# Stopper_alap_V14_qfn.net
KiCad netlist of a schematic drawn in EAGLE
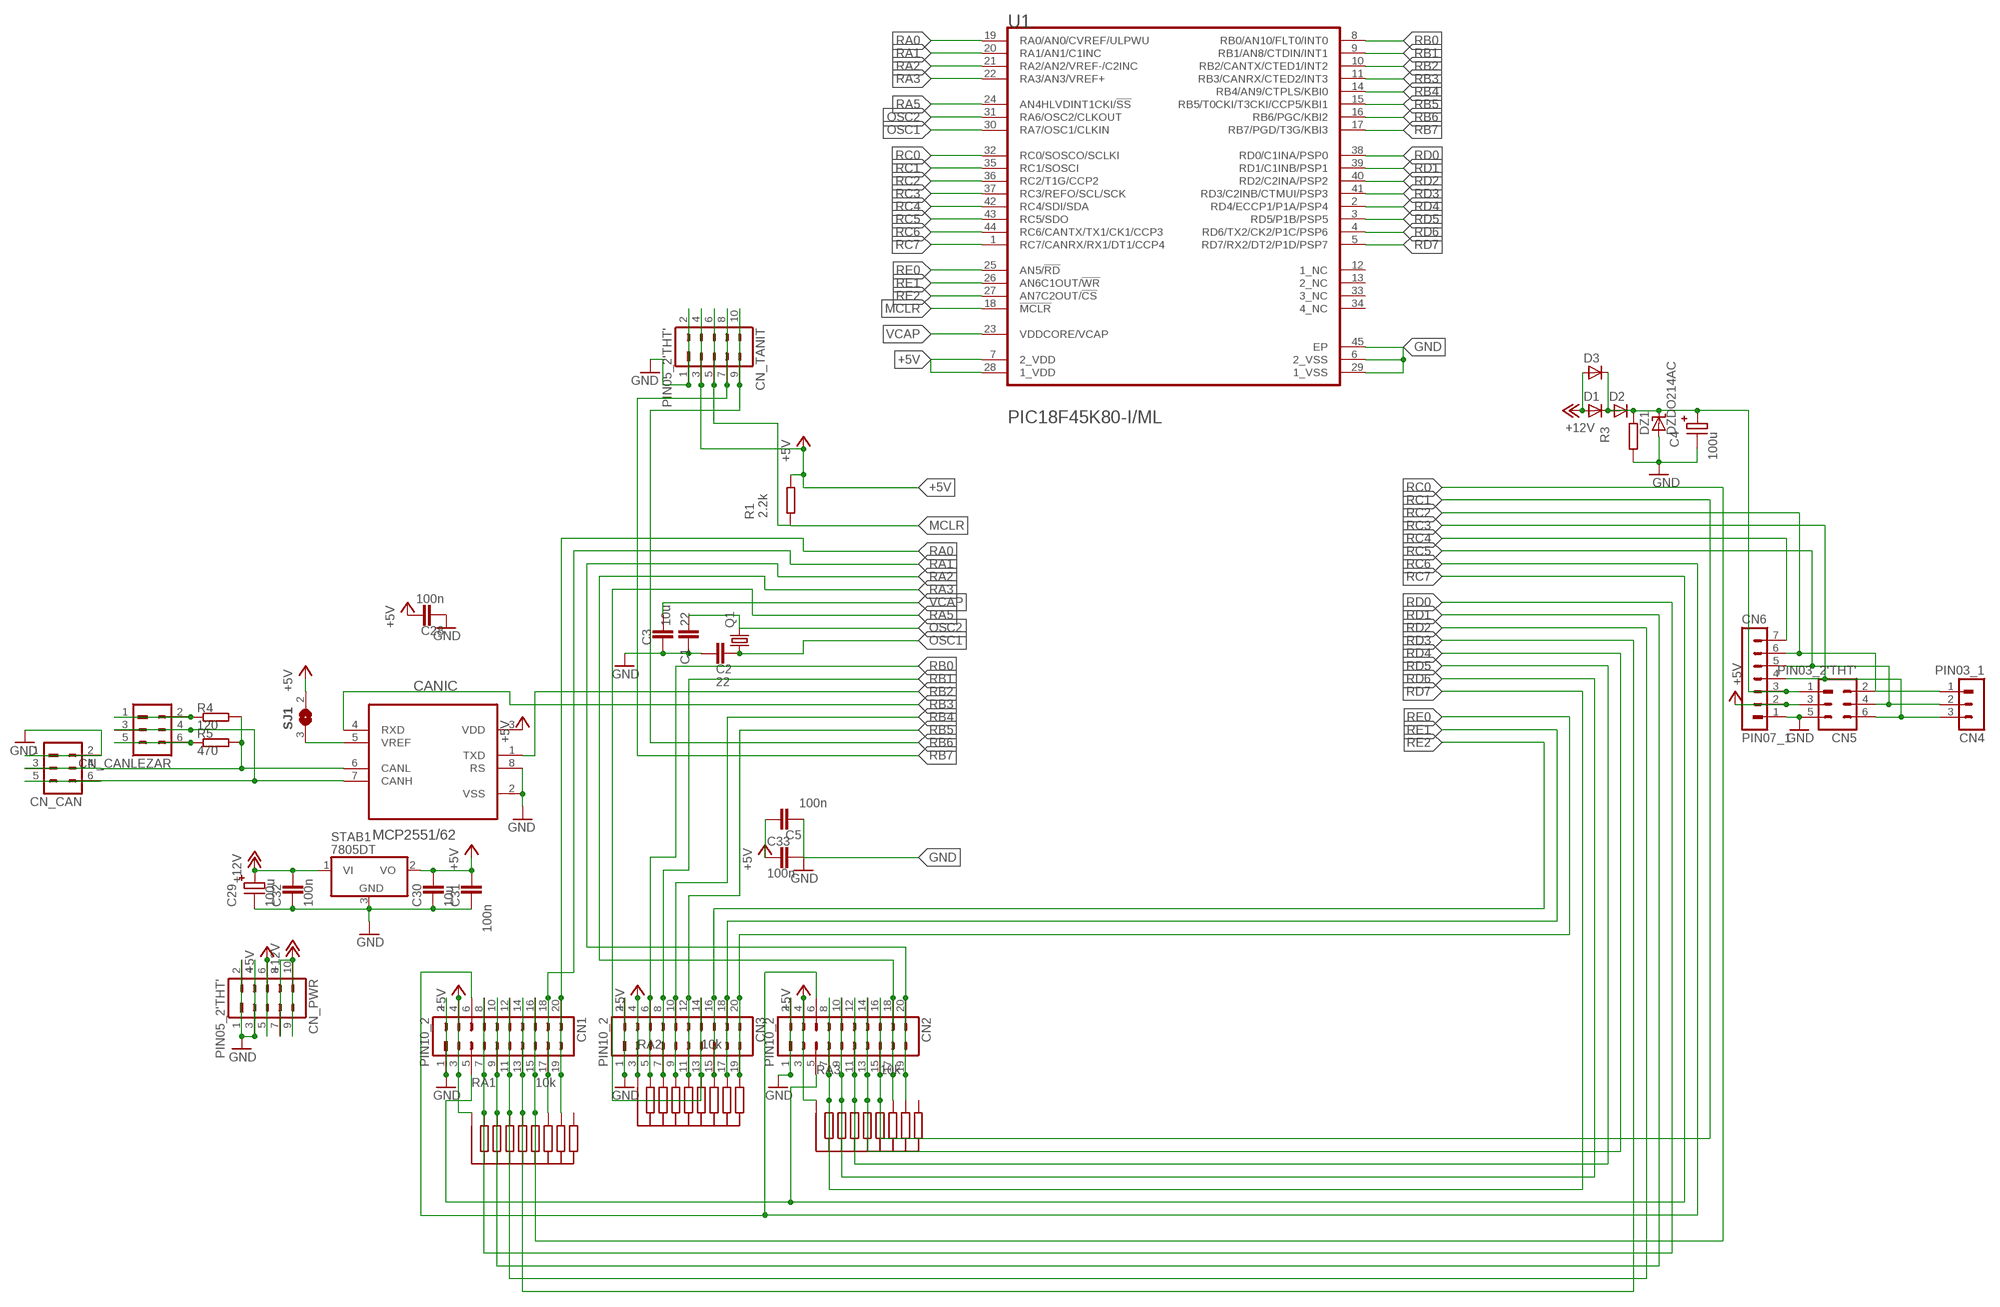
[diagram p0: schematic, sheet 1]

(export (version "E")
  (design (tool "Eeschema 10.0.6"))
  (components
    (comp (ref "C1")
      (value "22")
      (footprint "eagle-import:R0805")
      (libsource (lib "eagle-import") (part "C0805"))
    )
    (comp (ref "C2")
      (value "22")
      (footprint "eagle-import:R0805")
      (libsource (lib "eagle-import") (part "C0805"))
    )
    (comp (ref "C3")
      (value "10u")
      (footprint "eagle-import:R0805")
      (libsource (lib "eagle-import") (part "C0805"))
    )
    (comp (ref "C4")
      (value "100u")
      (footprint "eagle-import:C_EL1RASZT07")
      (libsource (lib "eagle-import") (part "C_EL1R07"))
    )
    (comp (ref "C5")
      (value "100n")
      (footprint "eagle-import:R0805")
      (libsource (lib "eagle-import") (part "C0805"))
    )
    (comp (ref "C28")
      (value "100n")
      (footprint "eagle-import:R0805")
      (libsource (lib "eagle-import") (part "C0805"))
    )
    (comp (ref "C29")
      (value "100u")
      (footprint "eagle-import:C_EL1RASZT07")
      (libsource (lib "eagle-import") (part "C_EL1R07"))
    )
    (comp (ref "C30")
      (value "10u")
      (footprint "eagle-import:R0805")
      (libsource (lib "eagle-import") (part "C0805"))
    )
    (comp (ref "C31")
      (value "100n")
      (footprint "eagle-import:R0805")
      (libsource (lib "eagle-import") (part "C0805"))
    )
    (comp (ref "C32")
      (value "100n")
      (footprint "eagle-import:R0805")
      (libsource (lib "eagle-import") (part "C0805"))
    )
    (comp (ref "C33")
      (value "100n")
      (footprint "eagle-import:R0805")
      (libsource (lib "eagle-import") (part "C0805"))
    )
    (comp (ref "CANIC")
      (value "MCP2551/62")
      (footprint "eagle-import:DIP254P762X432-8")
      (fields (field (name "MPN") "MCP2551-I/P"))
      (libsource (lib "eagle-import") (part "MCP2551-I/P"))
    )
    (comp (ref "CN1")
      (value "PIN10_2")
      (footprint "eagle-import:PIN10_2")
      (libsource (lib "eagle-import") (part "PIN10_2"))
    )
    (comp (ref "CN2")
      (value "PIN10_2")
      (footprint "eagle-import:PIN10_2")
      (libsource (lib "eagle-import") (part "PIN10_2"))
    )
    (comp (ref "CN3")
      (value "PIN10_2")
      (footprint "eagle-import:PIN10_2")
      (libsource (lib "eagle-import") (part "PIN10_2"))
    )
    (comp (ref "CN4")
      (value "PIN03_1")
      (footprint "eagle-import:PIN03_1")
      (libsource (lib "eagle-import") (part "PIN03_1"))
    )
    (comp (ref "CN5")
      (value "PIN03_2'THT'")
      (footprint "eagle-import:PIN03_2")
      (libsource (lib "eagle-import") (part "PIN03_2'THT'"))
    )
    (comp (ref "CN6")
      (value "PIN07_1")
      (footprint "eagle-import:PIN07_1")
      (libsource (lib "eagle-import") (part "PIN07_1"))
    )
    (comp (ref "CN_CAN")
      (value "PIN03_2'THT'")
      (footprint "eagle-import:PIN03_2")
      (libsource (lib "eagle-import") (part "PIN03_2'THT'"))
    )
    (comp (ref "CN_CANLEZAR")
      (value "PIN03_2'THT'")
      (footprint "eagle-import:PIN03_2")
      (libsource (lib "eagle-import") (part "PIN03_2'THT'"))
    )
    (comp (ref "CN_PWR")
      (value "PIN05_2'THT'")
      (footprint "eagle-import:PIN05_2")
      (libsource (lib "eagle-import") (part "PIN05_2'THT'"))
    )
    (comp (ref "CN_TANIT")
      (value "PIN05_2'THT'")
      (footprint "eagle-import:PIN05_2")
      (libsource (lib "eagle-import") (part "PIN05_2'THT'"))
    )
    (comp (ref "D1")
      (value "DDO214AC")
      (footprint "eagle-import:DO214AC")
      (libsource (lib "eagle-import") (part "DDO214AC"))
    )
    (comp (ref "D2")
      (value "DDO214AC")
      (footprint "eagle-import:DO214AC")
      (libsource (lib "eagle-import") (part "DDO214AC"))
    )
    (comp (ref "D3")
      (value "D1RNAGY")
      (footprint "eagle-import:D1RASZTNAGY")
      (libsource (lib "eagle-import") (part "D1RNAGY"))
    )
    (comp (ref "DZ1")
      (value "DZDO214AC")
      (footprint "eagle-import:DO214AC")
      (libsource (lib "eagle-import") (part "DZDO214AC"))
    )
    (comp (ref "Q1")
      (value "XTAL_2QS")
      (footprint "eagle-import:XTAL_QS")
      (libsource (lib "eagle-import") (part "XTAL_2QS"))
    )
    (comp (ref "R1")
      (value "2.2k")
      (footprint "eagle-import:R0805@1")
      (libsource (lib "eagle-import") (part "R_EU0805"))
    )
    (comp (ref "R3")
      (value "R_EU0805")
      (footprint "eagle-import:R0805@1")
      (libsource (lib "eagle-import") (part "R_EU0805"))
    )
    (comp (ref "R4")
      (value "120")
      (footprint "eagle-import:R0805@1")
      (libsource (lib "eagle-import") (part "R_EU0805"))
    )
    (comp (ref "R5")
      (value "470")
      (footprint "eagle-import:R0805@1")
      (libsource (lib "eagle-import") (part "R_EU0805"))
    )
    (comp (ref "RA1")
      (value "10k")
      (footprint "eagle-import:R_ARRAY")
      (libsource (lib "eagle-import") (part "R_ARRAY"))
    )
    (comp (ref "RA2")
      (value "10k")
      (footprint "eagle-import:R_ARRAY")
      (libsource (lib "eagle-import") (part "R_ARRAY"))
    )
    (comp (ref "RA3")
      (value "10k")
      (footprint "eagle-import:R_ARRAY")
      (libsource (lib "eagle-import") (part "R_ARRAY"))
    )
    (comp (ref "SJ1") (value "SJ") (footprint "eagle-import:SJ") (libsource (lib "eagle-import") (part "SJ")))
    (comp (ref "STAB1")
      (value "7805DT")
      (footprint "eagle-import:TO252")
      (libsource (lib "eagle-import") (part "78DT05"))
    )
    (comp (ref "U1")
      (value "MICROCHIP_PIC18F45K80-I-MLMICROCHIP_PIC18F45K80-I-ML_0_2")
      (footprint "eagle-import:MICROCHIP_PIC18F45K80-I-ML_2")
      (fields (field (name "MF") "Microchip") (field (name "MPN") "PIC18F45K80-I/ML"))
      (libsource (lib "eagle-import") (part "MICROCHIP_PIC18F45K80-I-MLMICROCHIP_PIC18F45K80-I-ML_0_2"))
    )
  )
  (nets
    (net (code "1") (name "+5V") (class "Default")
      (node (ref "C28") (pin "1") (pinfunction "1_1") (pintype "passive"))
      (node (ref "C30") (pin "1") (pinfunction "1_1") (pintype "passive"))
      (node (ref "C31") (pin "1") (pinfunction "1_1") (pintype "passive"))
      (node (ref "C33") (pin "2") (pinfunction "2_2") (pintype "passive"))
      (node (ref "C5") (pin "1") (pinfunction "1_1") (pintype "passive"))
      (node (ref "CANIC") (pin "3") (pinfunction "VDD_3") (pintype "power_in"))
      (node (ref "CN1") (pin "3") (pinfunction "3_3") (pintype "passive"))
      (node (ref "CN1") (pin "4") (pinfunction "4_4") (pintype "passive"))
      (node (ref "CN2") (pin "3") (pinfunction "3_3") (pintype "passive"))
      (node (ref "CN2") (pin "4") (pinfunction "4_4") (pintype "passive"))
      (node (ref "CN3") (pin "3") (pinfunction "3_3") (pintype "passive"))
      (node (ref "CN3") (pin "4") (pinfunction "4_4") (pintype "passive"))
      (node (ref "CN5") (pin "3") (pinfunction "3_3") (pintype "passive"))
      (node (ref "CN6") (pin "2") (pinfunction "2_2") (pintype "passive"))
      (node (ref "CN_PWR") (pin "5") (pinfunction "5_5") (pintype "passive"))
      (node (ref "CN_PWR") (pin "6") (pinfunction "6_6") (pintype "passive"))
      (node (ref "CN_TANIT") (pin "3") (pinfunction "3_3") (pintype "passive"))
      (node (ref "CN_TANIT") (pin "4") (pinfunction "4_4") (pintype "passive"))
      (node (ref "R1") (pin "2") (pinfunction "E_2") (pintype "passive"))
      (node (ref "RA1") (pin "P$1") (pinfunction "A_P$1") (pintype "passive"))
      (node (ref "RA2") (pin "P$1") (pinfunction "A_P$1") (pintype "passive"))
      (node (ref "RA3") (pin "P$1") (pinfunction "A_P$1") (pintype "passive"))
      (node (ref "SJ1") (pin "2") (pinfunction "2_2") (pintype "passive"))
      (node (ref "STAB1") (pin "2") (pinfunction "VO_2") (pintype "passive"))
      (node (ref "U1") (pin "28") (pinfunction "1_VDD_28") (pintype "power_in"))
      (node (ref "U1") (pin "7") (pinfunction "2_VDD_7") (pintype "power_in"))
    )
    (net (code "2") (name "+12V") (class "Default")
      (node (ref "C29") (pin "P+") (pinfunction "P+_P+") (pintype "passive"))
      (node (ref "C32") (pin "1") (pinfunction "1_1") (pintype "passive"))
      (node (ref "CN_PWR") (pin "10") (pinfunction "10_10") (pintype "passive"))
      (node (ref "CN_PWR") (pin "7") (pinfunction "7_7") (pintype "passive"))
      (node (ref "CN_PWR") (pin "8") (pinfunction "8_8") (pintype "passive"))
      (node (ref "CN_PWR") (pin "9") (pinfunction "9_9") (pintype "passive"))
      (node (ref "D1") (pin "A") (pinfunction "A_A") (pintype "passive"))
      (node (ref "D3") (pin "P$1") (pinfunction "A_P$1") (pintype "passive"))
      (node (ref "STAB1") (pin "1") (pinfunction "VI_1") (pintype "input"))
    )
    (net (code "3") (name "GND") (class "Default")
      (node (ref "C1") (pin "2") (pinfunction "2_2") (pintype "passive"))
      (node (ref "C2") (pin "2") (pinfunction "2_2") (pintype "passive"))
      (node (ref "C28") (pin "2") (pinfunction "2_2") (pintype "passive"))
      (node (ref "C29") (pin "P-") (pinfunction "P-_P-") (pintype "passive"))
      (node (ref "C3") (pin "2") (pinfunction "2_2") (pintype "passive"))
      (node (ref "C30") (pin "2") (pinfunction "2_2") (pintype "passive"))
      (node (ref "C31") (pin "2") (pinfunction "2_2") (pintype "passive"))
      (node (ref "C32") (pin "2") (pinfunction "2_2") (pintype "passive"))
      (node (ref "C33") (pin "1") (pinfunction "1_1") (pintype "passive"))
      (node (ref "C4") (pin "P-") (pinfunction "P-_P-") (pintype "passive"))
      (node (ref "C5") (pin "2") (pinfunction "2_2") (pintype "passive"))
      (node (ref "CANIC") (pin "2") (pinfunction "VSS_2") (pintype "power_in"))
      (node (ref "CANIC") (pin "8") (pinfunction "RS_8") (pintype "input"))
      (node (ref "CN1") (pin "1") (pinfunction "1_1") (pintype "passive"))
      (node (ref "CN1") (pin "2") (pinfunction "2_2") (pintype "passive"))
      (node (ref "CN2") (pin "1") (pinfunction "1_1") (pintype "passive"))
      (node (ref "CN2") (pin "2") (pinfunction "2_2") (pintype "passive"))
      (node (ref "CN3") (pin "1") (pinfunction "1_1") (pintype "passive"))
      (node (ref "CN3") (pin "2") (pinfunction "2_2") (pintype "passive"))
      (node (ref "CN5") (pin "5") (pinfunction "5_5") (pintype "passive"))
      (node (ref "CN6") (pin "1") (pinfunction "1_1") (pintype "passive"))
      (node (ref "CN_CAN") (pin "1") (pinfunction "1_1") (pintype "passive"))
      (node (ref "CN_CAN") (pin "2") (pinfunction "2_2") (pintype "passive"))
      (node (ref "CN_PWR") (pin "1") (pinfunction "1_1") (pintype "passive"))
      (node (ref "CN_PWR") (pin "2") (pinfunction "2_2") (pintype "passive"))
      (node (ref "CN_PWR") (pin "3") (pinfunction "3_3") (pintype "passive"))
      (node (ref "CN_PWR") (pin "4") (pinfunction "4_4") (pintype "passive"))
      (node (ref "CN_TANIT") (pin "1") (pinfunction "1_1") (pintype "passive"))
      (node (ref "CN_TANIT") (pin "2") (pinfunction "2_2") (pintype "passive"))
      (node (ref "DZ1") (pin "A") (pinfunction "A_A") (pintype "passive"))
      (node (ref "R3") (pin "1") (pinfunction "A_1") (pintype "passive"))
      (node (ref "STAB1") (pin "3") (pinfunction "GND_3") (pintype "passive"))
      (node (ref "U1") (pin "29") (pinfunction "1_VSS_29") (pintype "power_in"))
      (node (ref "U1") (pin "45") (pinfunction "EP_45") (pintype "power_in"))
      (node (ref "U1") (pin "6") (pinfunction "2_VSS_6") (pintype "power_in"))
    )
    (net (code "4") (name "MCLR") (class "Default")
      (node (ref "CN_TANIT") (pin "5") (pinfunction "5_5") (pintype "passive"))
      (node (ref "CN_TANIT") (pin "6") (pinfunction "6_6") (pintype "passive"))
      (node (ref "R1") (pin "1") (pinfunction "A_1") (pintype "passive"))
      (node (ref "U1") (pin "18") (pinfunction "~{MCLR}_18") (pintype "input"))
    )
    (net (code "5") (name "Net-(CANIC-CANH)") (class "Default")
      (node (ref "CANIC") (pin "7") (pinfunction "CANH_7") (pintype "bidirectional"))
      (node (ref "CN_CAN") (pin "5") (pinfunction "5_5") (pintype "passive"))
      (node (ref "CN_CAN") (pin "6") (pinfunction "6_6") (pintype "passive"))
      (node (ref "CN_CANLEZAR") (pin "3") (pinfunction "3_3") (pintype "passive"))
      (node (ref "CN_CANLEZAR") (pin "4") (pinfunction "4_4") (pintype "passive"))
    )
    (net (code "6") (name "Net-(CANIC-CANL)") (class "Default")
      (node (ref "CANIC") (pin "6") (pinfunction "CANL_6") (pintype "bidirectional"))
      (node (ref "CN_CAN") (pin "3") (pinfunction "3_3") (pintype "passive"))
      (node (ref "CN_CAN") (pin "4") (pinfunction "4_4") (pintype "passive"))
      (node (ref "R4") (pin "2") (pinfunction "E_2") (pintype "passive"))
      (node (ref "R5") (pin "1") (pinfunction "A_1") (pintype "passive"))
    )
    (net (code "7") (name "Net-(CANIC-VREF)") (class "Default")
      (node (ref "CANIC") (pin "5") (pinfunction "VREF_5") (pintype "output"))
      (node (ref "SJ1") (pin "3") (pinfunction "1_3") (pintype "passive"))
    )
    (net (code "8") (name "Net-(D3-C)") (class "Default")
      (node (ref "C4") (pin "P+") (pinfunction "P+_P+") (pintype "passive"))
      (node (ref "CN5") (pin "1") (pinfunction "1_1") (pintype "passive"))
      (node (ref "CN6") (pin "3") (pinfunction "3_3") (pintype "passive"))
      (node (ref "D1") (pin "C") (pinfunction "C_C") (pintype "passive"))
      (node (ref "D2") (pin "A") (pinfunction "A_A") (pintype "passive"))
      (node (ref "D2") (pin "C") (pinfunction "C_C") (pintype "passive"))
      (node (ref "D3") (pin "P$2") (pinfunction "C_P$2") (pintype "passive"))
      (node (ref "DZ1") (pin "C") (pinfunction "C_C") (pintype "passive"))
      (node (ref "R3") (pin "2") (pinfunction "E_2") (pintype "passive"))
    )
    (net (code "9") (name "Net-(R4-A)") (class "Default")
      (node (ref "CN_CANLEZAR") (pin "1") (pinfunction "1_1") (pintype "passive"))
      (node (ref "CN_CANLEZAR") (pin "2") (pinfunction "2_2") (pintype "passive"))
      (node (ref "R4") (pin "1") (pinfunction "A_1") (pintype "passive"))
    )
    (net (code "10") (name "Net-(R5-E)") (class "Default")
      (node (ref "CN_CANLEZAR") (pin "5") (pinfunction "5_5") (pintype "passive"))
      (node (ref "CN_CANLEZAR") (pin "6") (pinfunction "6_6") (pintype "passive"))
      (node (ref "R5") (pin "2") (pinfunction "E_2") (pintype "passive"))
    )
    (net (code "11") (name "OSC1") (class "Default")
      (node (ref "C2") (pin "1") (pinfunction "1_1") (pintype "passive"))
      (node (ref "Q1") (pin "1") (pinfunction "1_1") (pintype "passive"))
      (node (ref "U1") (pin "30") (pinfunction "RA7/OSC1/CLKIN_30") (pintype "bidirectional"))
    )
    (net (code "12") (name "OSC2") (class "Default")
      (node (ref "C1") (pin "1") (pinfunction "1_1") (pintype "passive"))
      (node (ref "Q1") (pin "2") (pinfunction "2_2") (pintype "passive"))
      (node (ref "U1") (pin "31") (pinfunction "RA6/OSC2/CLKOUT_31") (pintype "bidirectional"))
    )
    (net (code "13") (name "RA0") (class "Default")
      (node (ref "CN1") (pin "19") (pinfunction "19_19") (pintype "passive"))
      (node (ref "CN1") (pin "20") (pinfunction "20_20") (pintype "passive"))
      (node (ref "RA1") (pin "P$8") (pinfunction "E6_P$8") (pintype "passive"))
      (node (ref "U1") (pin "19") (pinfunction "RA0/AN0/CVREF/ULPWU_19") (pintype "bidirectional"))
    )
    (net (code "14") (name "RA1") (class "Default")
      (node (ref "CN1") (pin "17") (pinfunction "17_17") (pintype "passive"))
      (node (ref "CN1") (pin "18") (pinfunction "18_18") (pintype "passive"))
      (node (ref "RA1") (pin "P$7") (pinfunction "E5_P$7") (pintype "passive"))
      (node (ref "U1") (pin "20") (pinfunction "RA1/AN1/C1INC_20") (pintype "bidirectional"))
    )
    (net (code "15") (name "RA2") (class "Default")
      (node (ref "CN2") (pin "19") (pinfunction "19_19") (pintype "passive"))
      (node (ref "CN2") (pin "20") (pinfunction "20_20") (pintype "passive"))
      (node (ref "RA3") (pin "P$8") (pinfunction "E6_P$8") (pintype "passive"))
      (node (ref "U1") (pin "21") (pinfunction "RA2/AN2/VREF-/C2INC_21") (pintype "bidirectional"))
    )
    (net (code "16") (name "RA3") (class "Default")
      (node (ref "CN2") (pin "17") (pinfunction "17_17") (pintype "passive"))
      (node (ref "CN2") (pin "18") (pinfunction "18_18") (pintype "passive"))
      (node (ref "RA3") (pin "P$7") (pinfunction "E5_P$7") (pintype "passive"))
      (node (ref "U1") (pin "22") (pinfunction "RA3/AN3/VREF+_22") (pintype "bidirectional"))
    )
    (net (code "17") (name "RA5") (class "Default")
      (node (ref "CN3") (pin "13") (pinfunction "13_13") (pintype "passive"))
      (node (ref "CN3") (pin "14") (pinfunction "14_14") (pintype "passive"))
      (node (ref "RA2") (pin "P$6") (pinfunction "E4_P$6") (pintype "passive"))
      (node (ref "U1") (pin "24") (pinfunction "AN4HLVDINT1CKI/~{SS}_24") (pintype "bidirectional"))
    )
    (net (code "18") (name "RB0") (class "Default")
      (node (ref "CN3") (pin "5") (pinfunction "5_5") (pintype "passive"))
      (node (ref "CN3") (pin "6") (pinfunction "6_6") (pintype "passive"))
      (node (ref "RA2") (pin "P$2") (pinfunction "E_P$2") (pintype "passive"))
      (node (ref "U1") (pin "8") (pinfunction "RB0/AN10/FLT0/INT0_8") (pintype "bidirectional"))
    )
    (net (code "19") (name "RB1") (class "Default")
      (node (ref "CN3") (pin "7") (pinfunction "7_7") (pintype "passive"))
      (node (ref "CN3") (pin "8") (pinfunction "8_8") (pintype "passive"))
      (node (ref "RA2") (pin "P$3") (pinfunction "E1_P$3") (pintype "passive"))
      (node (ref "U1") (pin "9") (pinfunction "RB1/AN8/CTDIN/INT1_9") (pintype "bidirectional"))
    )
    (net (code "20") (name "RB2") (class "Default")
      (node (ref "CANIC") (pin "1") (pinfunction "TXD_1") (pintype "input"))
      (node (ref "U1") (pin "10") (pinfunction "RB2/CANTX/CTED1/INT2_10") (pintype "bidirectional"))
    )
    (net (code "21") (name "RB3") (class "Default")
      (node (ref "CANIC") (pin "4") (pinfunction "RXD_4") (pintype "output"))
      (node (ref "U1") (pin "11") (pinfunction "RB3/CANRX/CTED2/INT3_11") (pintype "bidirectional"))
    )
    (net (code "22") (name "RB4") (class "Default")
      (node (ref "CN3") (pin "10") (pinfunction "10_10") (pintype "passive"))
      (node (ref "CN3") (pin "9") (pinfunction "9_9") (pintype "passive"))
      (node (ref "RA2") (pin "P$4") (pinfunction "E2_P$4") (pintype "passive"))
      (node (ref "U1") (pin "14") (pinfunction "RB4/AN9/CTPLS/KBI0_14") (pintype "bidirectional"))
    )
    (net (code "23") (name "RB5") (class "Default")
      (node (ref "CN3") (pin "11") (pinfunction "11_11") (pintype "passive"))
      (node (ref "CN3") (pin "12") (pinfunction "12_12") (pintype "passive"))
      (node (ref "RA2") (pin "P$5") (pinfunction "E3_P$5") (pintype "passive"))
      (node (ref "U1") (pin "15") (pinfunction "RB5/T0CKI/T3CKI/CCP5/KBI1_15") (pintype "bidirectional"))
    )
    (net (code "24") (name "RB6") (class "Default")
      (node (ref "CN_TANIT") (pin "10") (pinfunction "10_10") (pintype "passive"))
      (node (ref "CN_TANIT") (pin "9") (pinfunction "9_9") (pintype "passive"))
      (node (ref "U1") (pin "16") (pinfunction "RB6/PGC/KBI2_16") (pintype "bidirectional"))
    )
    (net (code "25") (name "RB7") (class "Default")
      (node (ref "CN_TANIT") (pin "7") (pinfunction "7_7") (pintype "passive"))
      (node (ref "CN_TANIT") (pin "8") (pinfunction "8_8") (pintype "passive"))
      (node (ref "U1") (pin "17") (pinfunction "RB7/PGD/T3G/KBI3_17") (pintype "bidirectional"))
    )
    (net (code "26") (name "RC0") (class "Default")
      (node (ref "CN1") (pin "15") (pinfunction "15_15") (pintype "passive"))
      (node (ref "CN1") (pin "16") (pinfunction "16_16") (pintype "passive"))
      (node (ref "RA1") (pin "P$6") (pinfunction "E4_P$6") (pintype "passive"))
      (node (ref "U1") (pin "32") (pinfunction "RC0/SOSCO/SCLKI_32") (pintype "bidirectional"))
    )
    (net (code "27") (name "RC1") (class "Default")
      (node (ref "CN2") (pin "15") (pinfunction "15_15") (pintype "passive"))
      (node (ref "CN2") (pin "16") (pinfunction "16_16") (pintype "passive"))
      (node (ref "RA3") (pin "P$6") (pinfunction "E4_P$6") (pintype "passive"))
      (node (ref "U1") (pin "35") (pinfunction "RC1/SOSCI_35") (pintype "bidirectional"))
    )
    (net (code "28") (name "RC2") (class "Default")
      (node (ref "CN4") (pin "1") (pinfunction "1_1") (pintype "passive"))
      (node (ref "CN5") (pin "2") (pinfunction "2_2") (pintype "passive"))
      (node (ref "CN6") (pin "6") (pinfunction "6_6") (pintype "passive"))
      (node (ref "U1") (pin "36") (pinfunction "RC2/T1G/CCP2_36") (pintype "bidirectional"))
    )
    (net (code "29") (name "RC3") (class "Default")
      (node (ref "CN4") (pin "3") (pinfunction "3_3") (pintype "passive"))
      (node (ref "CN5") (pin "6") (pinfunction "6_6") (pintype "passive"))
      (node (ref "CN6") (pin "4") (pinfunction "4_4") (pintype "passive"))
      (node (ref "U1") (pin "37") (pinfunction "RC3/REFO/SCL/SCK_37") (pintype "bidirectional"))
    )
    (net (code "30") (name "RC4") (class "Default")
      (node (ref "CN6") (pin "7") (pinfunction "7_7") (pintype "passive"))
      (node (ref "U1") (pin "42") (pinfunction "RC4/SDI/SDA_42") (pintype "bidirectional"))
    )
    (net (code "31") (name "RC5") (class "Default")
      (node (ref "CN4") (pin "2") (pinfunction "2_2") (pintype "passive"))
      (node (ref "CN5") (pin "4") (pinfunction "4_4") (pintype "passive"))
      (node (ref "CN6") (pin "5") (pinfunction "5_5") (pintype "passive"))
      (node (ref "U1") (pin "43") (pinfunction "RC5/SDO_43") (pintype "bidirectional"))
    )
    (net (code "32") (name "RC6") (class "Default")
      (node (ref "CN1") (pin "6") (pinfunction "6_6") (pintype "passive"))
      (node (ref "CN2") (pin "6") (pinfunction "6_6") (pintype "passive"))
      (node (ref "U1") (pin "44") (pinfunction "RC6/CANTX/TX1/CK1/CCP3_44") (pintype "bidirectional"))
    )
    (net (code "33") (name "RC7") (class "Default")
      (node (ref "CN1") (pin "5") (pinfunction "5_5") (pintype "passive"))
      (node (ref "CN2") (pin "5") (pinfunction "5_5") (pintype "passive"))
      (node (ref "U1") (pin "1") (pinfunction "RC7/CANRX/RX1/DT1/CCP4_1") (pintype "bidirectional"))
    )
    (net (code "34") (name "RD0") (class "Default")
      (node (ref "CN1") (pin "7") (pinfunction "7_7") (pintype "passive"))
      (node (ref "CN1") (pin "8") (pinfunction "8_8") (pintype "passive"))
      (node (ref "RA1") (pin "P$2") (pinfunction "E_P$2") (pintype "passive"))
      (node (ref "U1") (pin "38") (pinfunction "RD0/C1INA/PSP0_38") (pintype "bidirectional"))
    )
    (net (code "35") (name "RD1") (class "Default")
      (node (ref "CN1") (pin "10") (pinfunction "10_10") (pintype "passive"))
      (node (ref "CN1") (pin "9") (pinfunction "9_9") (pintype "passive"))
      (node (ref "RA1") (pin "P$3") (pinfunction "E1_P$3") (pintype "passive"))
      (node (ref "U1") (pin "39") (pinfunction "RD1/C1INB/PSP1_39") (pintype "bidirectional"))
    )
    (net (code "36") (name "RD2") (class "Default")
      (node (ref "CN1") (pin "11") (pinfunction "11_11") (pintype "passive"))
      (node (ref "CN1") (pin "12") (pinfunction "12_12") (pintype "passive"))
      (node (ref "RA1") (pin "P$4") (pinfunction "E2_P$4") (pintype "passive"))
      (node (ref "U1") (pin "40") (pinfunction "RD2/C2INA/PSP2_40") (pintype "bidirectional"))
    )
    (net (code "37") (name "RD3") (class "Default")
      (node (ref "CN1") (pin "13") (pinfunction "13_13") (pintype "passive"))
      (node (ref "CN1") (pin "14") (pinfunction "14_14") (pintype "passive"))
      (node (ref "RA1") (pin "P$5") (pinfunction "E3_P$5") (pintype "passive"))
      (node (ref "U1") (pin "41") (pinfunction "RD3/C2INB/CTMUI/PSP3_41") (pintype "bidirectional"))
    )
    (net (code "38") (name "RD4") (class "Default")
      (node (ref "CN2") (pin "13") (pinfunction "13_13") (pintype "passive"))
      (node (ref "CN2") (pin "14") (pinfunction "14_14") (pintype "passive"))
      (node (ref "RA3") (pin "P$5") (pinfunction "E3_P$5") (pintype "passive"))
      (node (ref "U1") (pin "2") (pinfunction "RD4/ECCP1/P1A/PSP4_2") (pintype "bidirectional"))
    )
    (net (code "39") (name "RD5") (class "Default")
      (node (ref "CN2") (pin "11") (pinfunction "11_11") (pintype "passive"))
      (node (ref "CN2") (pin "12") (pinfunction "12_12") (pintype "passive"))
      (node (ref "RA3") (pin "P$4") (pinfunction "E2_P$4") (pintype "passive"))
      (node (ref "U1") (pin "3") (pinfunction "RD5/P1B/PSP5_3") (pintype "bidirectional"))
    )
    (net (code "40") (name "RD6") (class "Default")
      (node (ref "CN2") (pin "10") (pinfunction "10_10") (pintype "passive"))
      (node (ref "CN2") (pin "9") (pinfunction "9_9") (pintype "passive"))
      (node (ref "RA3") (pin "P$3") (pinfunction "E1_P$3") (pintype "passive"))
      (node (ref "U1") (pin "4") (pinfunction "RD6/TX2/CK2/P1C/PSP6_4") (pintype "bidirectional"))
    )
    (net (code "41") (name "RD7") (class "Default")
      (node (ref "CN2") (pin "7") (pinfunction "7_7") (pintype "passive"))
      (node (ref "CN2") (pin "8") (pinfunction "8_8") (pintype "passive"))
      (node (ref "RA3") (pin "P$2") (pinfunction "E_P$2") (pintype "passive"))
      (node (ref "U1") (pin "5") (pinfunction "RD7/RX2/DT2/P1D/PSP7_5") (pintype "bidirectional"))
    )
    (net (code "42") (name "RE0") (class "Default")
      (node (ref "CN3") (pin "19") (pinfunction "19_19") (pintype "passive"))
      (node (ref "CN3") (pin "20") (pinfunction "20_20") (pintype "passive"))
      (node (ref "RA2") (pin "P$9") (pinfunction "E7_P$9") (pintype "passive"))
      (node (ref "U1") (pin "25") (pinfunction "AN5/~{RD}_25") (pintype "bidirectional"))
    )
    (net (code "43") (name "RE1") (class "Default")
      (node (ref "CN3") (pin "17") (pinfunction "17_17") (pintype "passive"))
      (node (ref "CN3") (pin "18") (pinfunction "18_18") (pintype "passive"))
      (node (ref "RA2") (pin "P$8") (pinfunction "E6_P$8") (pintype "passive"))
      (node (ref "U1") (pin "26") (pinfunction "AN6C1OUT/~{WR}_26") (pintype "bidirectional"))
    )
    (net (code "44") (name "RE2") (class "Default")
      (node (ref "CN3") (pin "15") (pinfunction "15_15") (pintype "passive"))
      (node (ref "CN3") (pin "16") (pinfunction "16_16") (pintype "passive"))
      (node (ref "RA2") (pin "P$7") (pinfunction "E5_P$7") (pintype "passive"))
      (node (ref "U1") (pin "27") (pinfunction "AN7C2OUT/~{CS}_27") (pintype "bidirectional"))
    )
    (net (code "45") (name "VCAP") (class "Default")
      (node (ref "C3") (pin "1") (pinfunction "1_1") (pintype "passive"))
      (node (ref "U1") (pin "23") (pinfunction "VDDCORE/VCAP_23") (pintype "power_in"))
    )
    (net (code "46") (name "unconnected-(RA1-E7-PadP$9)") (class "Default")
      (node (ref "RA1") (pin "P$9") (pinfunction "E7_P$9") (pintype "passive"))
    )
    (net (code "47") (name "unconnected-(RA3-E7-PadP$9)") (class "Default")
      (node (ref "RA3") (pin "P$9") (pinfunction "E7_P$9") (pintype "passive"))
    )
    (net (code "48") (name "unconnected-(U1-1_NC-Pad12)") (class "Default")
      (node (ref "U1") (pin "12") (pinfunction "1_NC_12") (pintype "passive"))
    )
    (net (code "49") (name "unconnected-(U1-2_NC-Pad13)") (class "Default")
      (node (ref "U1") (pin "13") (pinfunction "2_NC_13") (pintype "passive"))
    )
    (net (code "50") (name "unconnected-(U1-3_NC-Pad33)") (class "Default")
      (node (ref "U1") (pin "33") (pinfunction "3_NC_33") (pintype "passive"))
    )
    (net (code "51") (name "unconnected-(U1-4_NC-Pad34)") (class "Default")
      (node (ref "U1") (pin "34") (pinfunction "4_NC_34") (pintype "passive"))
    )
  )
)
